# Sender_Power.net
KiCad netlist of a schematic drawn in Altium Designer
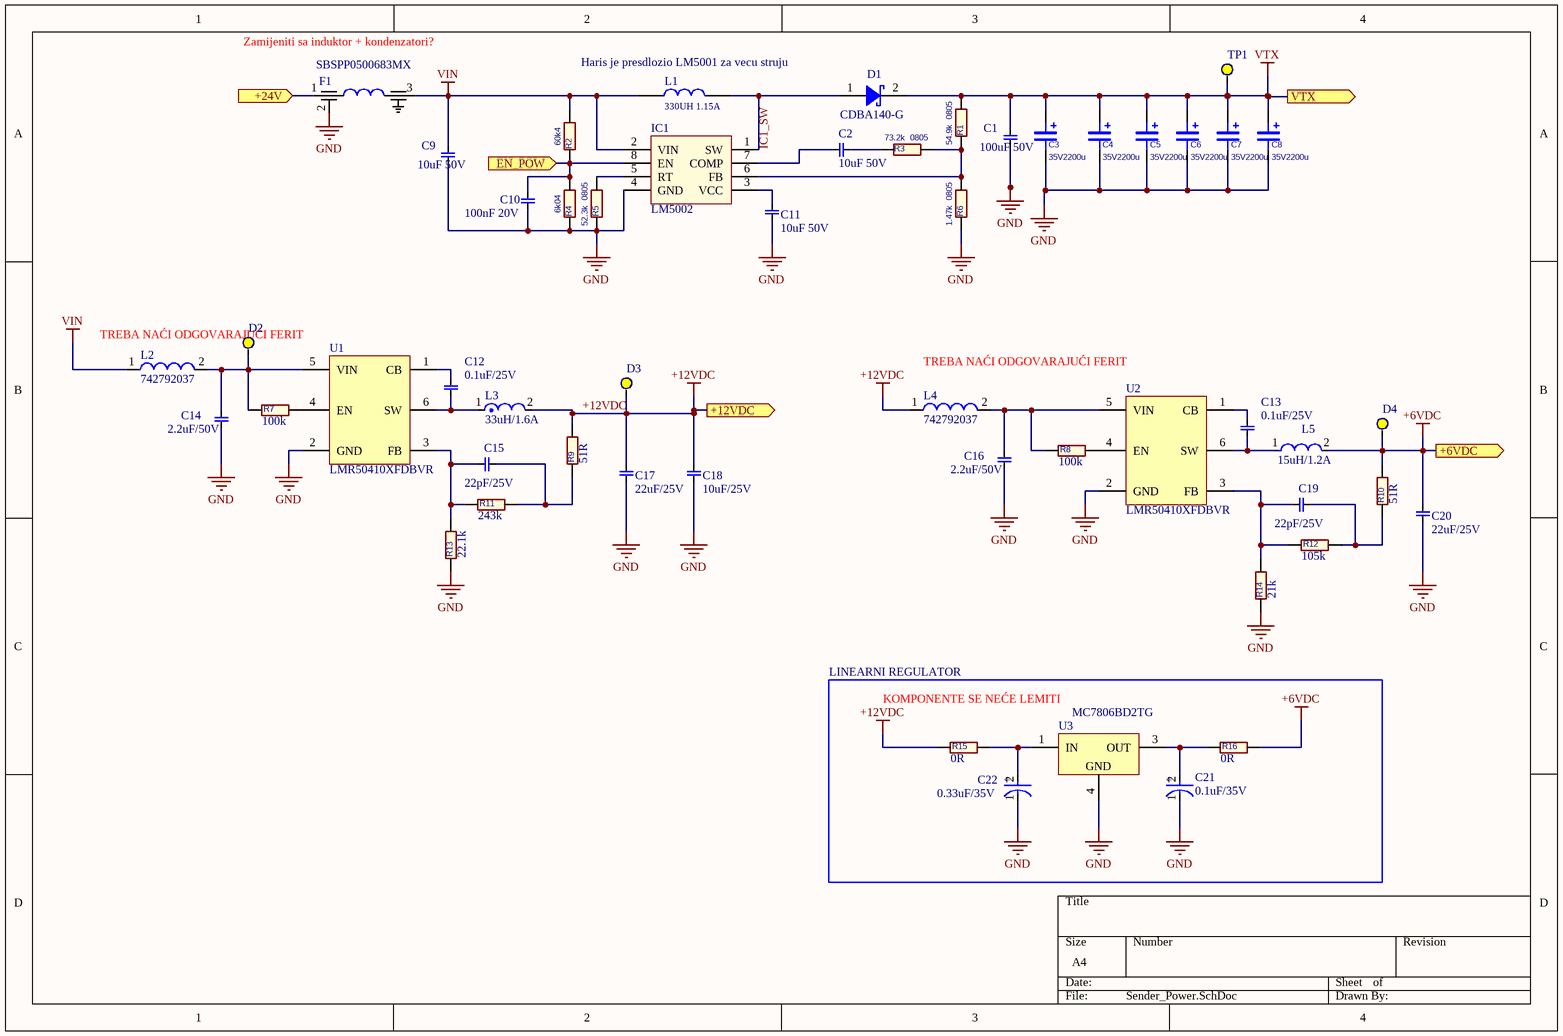
[diagram p0: Sender_Power.SchDoc]

(export (version "E")
  (design (tool "Eeschema 10.0.6"))
  (components
    (comp (ref "C1")
      (value "100uF 50V")
      (footprint "C-0805")
      (fields (field (name "TOLERANCE") "±10%"))
      (libsource (lib "Elreg_Sender") (part "C-0805_10uF"))
    )
    (comp (ref "C2")
      (value "10uF 50V")
      (footprint "C-0603")
      (fields (field (name "TOLERANCE") "±10%"))
      (libsource (lib "Elreg_Sender") (part "C-0805_10uF"))
    )
    (comp (ref "C3")
      (value "35V2200u")
      (footprint "CAP_16X25")
      (description "Capacitor")
      (fields
        (field (name "MANUFACTURER") "Kemet")
        (field (name "MANUFACTURER PART NUMBER") "ESH228M035AM7AA")
      )
      (libsource (lib "Elreg_Sender") (part "CAP_2200uF_35V"))
    )
    (comp (ref "C4")
      (value "35V2200u")
      (footprint "CAP_16X25")
      (description "Capacitor")
      (fields
        (field (name "MANUFACTURER") "Kemet")
        (field (name "MANUFACTURER PART NUMBER") "ESH228M035AM7AA")
      )
      (libsource (lib "Elreg_Sender") (part "CAP_2200uF_35V"))
    )
    (comp (ref "C5")
      (value "35V2200u")
      (footprint "CAP_16X25")
      (description "Capacitor")
      (fields
        (field (name "MANUFACTURER") "Kemet")
        (field (name "MANUFACTURER PART NUMBER") "ESH228M035AM7AA")
      )
      (libsource (lib "Elreg_Sender") (part "CAP_2200uF_35V"))
    )
    (comp (ref "C6")
      (value "35V2200u")
      (footprint "CAP_16X25")
      (description "Capacitor")
      (fields
        (field (name "MANUFACTURER") "Kemet")
        (field (name "MANUFACTURER PART NUMBER") "ESH228M035AM7AA")
      )
      (libsource (lib "Elreg_Sender") (part "CAP_2200uF_35V"))
    )
    (comp (ref "C7")
      (value "35V2200u")
      (footprint "CAP_16X25")
      (description "Capacitor")
      (fields
        (field (name "MANUFACTURER") "Kemet")
        (field (name "MANUFACTURER PART NUMBER") "ESH228M035AM7AA")
      )
      (libsource (lib "Elreg_Sender") (part "CAP_2200uF_35V"))
    )
    (comp (ref "C8")
      (value "35V2200u")
      (footprint "CAP_16X25")
      (description "Capacitor")
      (fields
        (field (name "MANUFACTURER") "Kemet")
        (field (name "MANUFACTURER PART NUMBER") "ESH228M035AM7AA")
      )
      (libsource (lib "Elreg_Sender") (part "CAP_2200uF_35V"))
    )
    (comp (ref "C9")
      (value "10uF 50V")
      (footprint "C-0805")
      (fields (field (name "TOLERANCE") "±10%"))
      (libsource (lib "Elreg_Sender") (part "C-0805_10uF"))
    )
    (comp (ref "C10")
      (value "100nF 20V")
      (footprint "C-0603")
      (fields (field (name "TOLERANCE") "±10%"))
      (libsource (lib "Elreg_Sender") (part "C-0805_100nF"))
    )
    (comp (ref "C11")
      (value "10uF 50V")
      (footprint "C-0603")
      (fields (field (name "TOLERANCE") "±10%"))
      (libsource (lib "Elreg_Sender") (part "C-0805_10uF"))
    )
    (comp (ref "C12")
      (value "0.1uF/25V")
      (footprint "C-0603")
      (description "0.1µF ±5% 25V Ceramic Capacitor X7R 0603 (1608 Metric)")
      (fields
        (field (name "MANUFACTURER") "Kyocera AVX")
        (field (name "MANUFACTURER PART NUMBER") "06033C104JAZ2A")
      )
      (libsource (lib "New_Library") (part "06033C104JAZ2A"))
    )
    (comp (ref "C13")
      (value "0.1uF/25V")
      (footprint "C-0603")
      (description "0.1µF ±5% 25V Ceramic Capacitor X7R 0603 (1608 Metric)")
      (fields
        (field (name "MANUFACTURER") "Kyocera AVX")
        (field (name "MANUFACTURER PART NUMBER") "06033C104JAZ2A")
      )
      (libsource (lib "New_Library") (part "06033C104JAZ2A"))
    )
    (comp (ref "C14")
      (value "2.2uF/50V")
      (footprint "FP-CL31-IPC_B")
      (description "Cap Ceramic 2.2uF 50V X7R ±10% SMD 1206 +125°C Embossed T/R")
      (fields (field (name "TOLERANCE") "10%"))
      (libsource (lib "New_Library") (part "CL31B225KBHVPNE"))
    )
    (comp (ref "C15")
      (value "22pF/25V")
      (footprint "C-0603")
      (description "22pF ±10% 25V Ceramic Capacitor C0G, NP0 0603 (1608 Metric)")
      (fields
        (field (name "MANUFACTURER") "KEMET")
        (field (name "MANUFACTURER PART NUMBER") "C0603C220K3GACTU")
      )
      (libsource (lib "New_Library") (part "C0603C220K3GACTU"))
    )
    (comp (ref "C16")
      (value "2.2uF/50V")
      (footprint "FP-CL31-IPC_B")
      (description "Cap Ceramic 2.2uF 50V X7R ±10% SMD 1206 +125°C Embossed T/R")
      (fields (field (name "TOLERANCE") "10%"))
      (libsource (lib "New_Library") (part "CL31B225KBHVPNE"))
    )
    (comp (ref "C17")
      (value "22uF/25V")
      (footprint "CAP-1210")
      (description "22µF ±10% 25V Ceramic Capacitor X7R 1210 (3225 Metric)")
      (fields
        (field (name "MANUFACTURER") "Samsung")
        (field (name "MANUFACTURER PART NUMBER") "CL32B226KAJNNNE")
      )
      (libsource (lib "New_Library") (part "CL32B226KAJNNNE"))
    )
    (comp (ref "C18")
      (value "10uF/25V")
      (footprint "C-1206 (3216 metric)")
      (description "10µF ±10% 25V Ceramic Capacitor X7R 1206 (3216 Metric)")
      (fields
        (field (name "MANUFACTURER") "Samsung")
        (field (name "MANUFACTURER PART NUMBER") "CL31B106KAHNNNE")
      )
      (libsource (lib "New_Library") (part "CL31B106KAHNNNE"))
    )
    (comp (ref "C19")
      (value "22pF/25V")
      (footprint "C-0603")
      (description "22pF ±10% 25V Ceramic Capacitor C0G, NP0 0603 (1608 Metric)")
      (fields
        (field (name "MANUFACTURER") "KEMET")
        (field (name "MANUFACTURER PART NUMBER") "C0603C220K3GACTU")
      )
      (libsource (lib "New_Library") (part "C0603C220K3GACTU"))
    )
    (comp (ref "C20")
      (value "22uF/25V")
      (footprint "CAP-1210")
      (description "22µF ±10% 25V Ceramic Capacitor X7R 1210 (3225 Metric)")
      (fields
        (field (name "MANUFACTURER") "Samsung")
        (field (name "MANUFACTURER PART NUMBER") "CL32B226KAJNNNE")
      )
      (libsource (lib "New_Library") (part "CL32B226KAJNNNE"))
    )
    (comp (ref "C21")
      (value "0.1uF/35V")
      (footprint "FP-UUP1H0R1MCL1GS-MFG")
      (description "0.1µF 50V Aluminum Electrolytic Capacitors Radial, Can - SMD  1000 Hrs @ 105°C")
      (fields (field (name "TOLERANCE") "20%"))
      (libsource (lib "New_Library") (part "UUP1H0R1MCL1GS"))
    )
    (comp (ref "C22")
      (value "0.33uF/35V")
      (footprint "FP-UUP1H0R1MCL1GS-MFG")
      (description "0.33µF 50V Aluminum Electrolytic Capacitors Radial, Can - SMD  2000 Hrs @ 85°C")
      (fields
        (field (name "MANUFACTURER") "Nichicon")
        (field (name "MANUFACTURER PART NUMBER") "UZS1HR33MCL1GB")
      )
      (libsource (lib "New_Library") (part "UZS1HR33MCL1GB"))
    )
    (comp (ref "D1")
      (value "DIODE SCHOTTKY 40V 1A DO214AC")
      (footprint "DFN380P520X45-2N")
      (fields
        (field (name "MANUFACTURER PART NUMBER 1") "CDBA140-G")
        (field (name "BASE PART NUMBER") "CDBA140")
      )
      (libsource (lib "Elreg_Sender") (part "DIODE SCHOTTKY 40V 1A DO214AC"))
    )
    (comp (ref "D2")
      (value "Test_Point")
      (footprint "Test_Point")
      (libsource (lib "New_Library") (part "Test_Point"))
    )
    (comp (ref "D3")
      (value "Test_Point")
      (footprint "Test_Point")
      (libsource (lib "New_Library") (part "Test_Point"))
    )
    (comp (ref "D4")
      (value "Test_Point")
      (footprint "Test_Point")
      (libsource (lib "New_Library") (part "Test_Point"))
    )
    (comp (ref "F1")
      (value "SBSPP0500683MX")
      (footprint "Filter_SBSPP0500")
      (libsource (lib "Elreg_Sender") (part "Filter_SBSPP0500683MX"))
    )
    (comp (ref "IC1")
      (value "LM5002")
      (footprint "SOIC127P600X205-8N")
      (fields (field (name "BASE PART NUMBER") "LM5002"))
      (libsource (lib "New_Library") (part "LM5002"))
    )
    (comp (ref "L1")
      (value "330UH 1.15A")
      (footprint "IND")
      (libsource (lib "Elreg_Sender") (part "FIXED IND 330UH 1.15A 580 MOHM"))
    )
    (comp (ref "L2")
      (value "742792037")
      (footprint "SMD-0805")
      (description "SMD EMI Suppression Ferrite Bead WE-CBF, Z = 330 Ohm")
      (libsource (lib "New_Library") (part "742792037"))
    )
    (comp (ref "L3")
      (value "33uH/1.6A")
      (footprint "FP-DS104C2-MFG")
      (description "Shielded Wirewound Inductor 33uH 20% 1600mA 0.125Ω SMD")
      (fields (field (name "TOLERANCE") "20%"))
      (libsource (lib "New_Library") (part "#B952AS-H-330M=P3"))
    )
    (comp (ref "L4")
      (value "742792037")
      (footprint "SMD-0805")
      (description "SMD EMI Suppression Ferrite Bead WE-CBF, Z = 330 Ohm")
      (libsource (lib "New_Library") (part "742792037"))
    )
    (comp (ref "L5")
      (value "15uH/1.2A")
      (footprint "FP-LQH5BPB_T0-MFG")
      (description "15µH Shielded Wirewound Inductor 1.2A 187mOhm Max Nonstandard")
      (fields (field (name "TOLERANCE") "20%"))
      (libsource (lib "New_Library") (part "LQH5BPN150MT0L"))
    )
    (comp (ref "R1")
      (value "54.9k  0805")
      (footprint "R-0603")
      (description "RES xx OHM 1/8W 5% 0805 SMD")
      (libsource (lib "Elreg (Skipper)") (part "CRCW0805xxxxJN Default"))
    )
    (comp (ref "R2")
      (value "60k4")
      (footprint "R-0603")
      (description "RES 1 KOHM 1/8W 1% 0805 SMD")
      (fields (field (name "TOLERANCE") "±1%"))
      (libsource (lib "Elreg (Skipper)") (part "CRCW08051K00FKEA"))
    )
    (comp (ref "R3")
      (value "73.2k  0805")
      (footprint "R-0603")
      (description "RES xx OHM 1/8W 5% 0805 SMD")
      (libsource (lib "") (part "CRCW0805xxxxJN Default_1"))
    )
    (comp (ref "R4")
      (value "6k04")
      (footprint "R-0603")
      (description "RES 1 KOHM 1/8W 1% 0805 SMD")
      (fields (field (name "TOLERANCE") "±1%"))
      (libsource (lib "Elreg (Skipper)") (part "CRCW08051K00FKEA"))
    )
    (comp (ref "R5")
      (value "52.3k  0805")
      (footprint "R-0603")
      (description "RES xx OHM 1/8W 5% 0805 SMD")
      (libsource (lib "Elreg (Skipper)") (part "CRCW0805xxxxJN Default"))
    )
    (comp (ref "R6")
      (value "1.47k  0805")
      (footprint "R-0603")
      (description "RES xx OHM 1/8W 5% 0805 SMD")
      (libsource (lib "Elreg (Skipper)") (part "CRCW0805xxxxJN Default"))
    )
    (comp (ref "R7")
      (value "100k")
      (footprint "R-0603")
      (description "100 kOhms ±0.5% 0.063W, 1/16W Chip Resistor 0603 (1608 Metric)  Thin Film")
      (fields
        (field (name "MANUFACTURER") "Susumu")
        (field (name "MANUFACTURER PART NUMBER") "RR0816P-104-D")
      )
      (libsource (lib "New_Library") (part "RR0816P-104-D"))
    )
    (comp (ref "R8")
      (value "100k")
      (footprint "R-0603")
      (description "100 kOhms ±0.5% 0.063W, 1/16W Chip Resistor 0603 (1608 Metric)  Thin Film")
      (fields
        (field (name "MANUFACTURER") "Susumu")
        (field (name "MANUFACTURER PART NUMBER") "RR0816P-104-D")
      )
      (libsource (lib "New_Library") (part "RR0816P-104-D"))
    )
    (comp (ref "R9")
      (value "51R")
      (footprint "R-0603")
      (description "51 Ohms ±0.5% 0.063W, 1/16W Chip Resistor 0603 (1608 Metric)  Thin Film")
      (fields
        (field (name "MANUFACTURER") "Susumu")
        (field (name "MANUFACTURER PART NUMBER") "RR0816Q-510-D")
      )
      (libsource (lib "New_Library") (part "RR0816Q-510-D"))
    )
    (comp (ref "R10")
      (value "51R")
      (footprint "R-0603")
      (description "51 Ohms ±0.5% 0.063W, 1/16W Chip Resistor 0603 (1608 Metric)  Thin Film")
      (fields
        (field (name "MANUFACTURER") "Susumu")
        (field (name "MANUFACTURER PART NUMBER") "RR0816Q-510-D")
      )
      (libsource (lib "New_Library") (part "RR0816Q-510-D"))
    )
    (comp (ref "R11")
      (value "243k")
      (footprint "R-0603")
      (description "243 kOhms ±0.5% 0.063W, 1/16W Chip Resistor 0603 (1608 Metric)  Thin Film")
      (fields
        (field (name "MANUFACTURER") "Susumu")
        (field (name "MANUFACTURER PART NUMBER") "RR0816P-2433-D-38D")
      )
      (libsource (lib "New_Library") (part "RR0816P-2433-D-38D"))
    )
    (comp (ref "R12")
      (value "105k")
      (footprint "R-0603")
      (description "105 kOhms ±0.1% 0.063W, 1/16W Chip Resistor 0603 (1608 Metric)  Thin Film")
      (fields
        (field (name "MANUFACTURER") "TE Connectivity")
        (field (name "MANUFACTURER PART NUMBER") "RN73C1J105KBTDF")
      )
      (libsource (lib "New_Library") (part "RN73C1J105KBTD"))
    )
    (comp (ref "R13")
      (value "22.1k")
      (footprint "R-0603")
      (description "22.1 kOhms ±0.5% 0.063W, 1/16W Chip Resistor 0603 (1608 Metric)  Thin Film")
      (fields
        (field (name "MANUFACTURER") "Susumu")
        (field (name "MANUFACTURER PART NUMBER") "RR0816P-2212-D-34C")
      )
      (libsource (lib "New_Library") (part "RR0816P-2212-D-34C"))
    )
    (comp (ref "R14")
      (value "21k")
      (footprint "R-0603")
      (description "21 kOhms ±0.5% 0.063W, 1/16W Chip Resistor 0603 (1608 Metric)  Thin Film")
      (fields
        (field (name "MANUFACTURER") "Susumu")
        (field (name "MANUFACTURER PART NUMBER") "RR0816P-2102-D-32C")
      )
      (libsource (lib "New_Library") (part "RR0816P-2102-D-32C"))
    )
    (comp (ref "R15")
      (value "0R")
      (footprint "RES-0805")
      (description "0 Ohms Jumper 0.125W, 1/8W Chip Resistor 0805 (2012 Metric) Moisture Resistant Thick Film")
      (libsource (lib "New_Library") (part "RC0805JR-070RL"))
    )
    (comp (ref "R16")
      (value "0R")
      (footprint "RES-0805")
      (description "0 Ohms Jumper 0.125W, 1/8W Chip Resistor 0805 (2012 Metric) Moisture Resistant Thick Film")
      (libsource (lib "New_Library") (part "RC0805JR-070RL"))
    )
    (comp (ref "TP1")
      (value "Test_Point")
      (footprint "Test_Point")
      (libsource (lib "New_Library") (part "Test_Point"))
    )
    (comp (ref "U1")
      (value "LMR50410XFDBVR")
      (footprint "SOT-23")
      (description "Buck Switching Regulator IC Positive Adjustable 1V 1 Output 1A SOT-23-6")
      (fields (field (name "MANUFACTURER") "Texas Instruments"))
      (libsource (lib "New_Library") (part "LMR50410XFDBVR"))
    )
    (comp (ref "U2")
      (value "LMR50410XFDBVR")
      (footprint "SOT-23")
      (description "Buck Switching Regulator IC Positive Adjustable 1V 1 Output 1A SOT-23-6")
      (fields (field (name "MANUFACTURER") "Texas Instruments"))
      (libsource (lib "New_Library") (part "LMR50410XFDBVR"))
    )
    (comp (ref "U3")
      (value "MC7806BD2TG")
      (footprint "D2PAK")
      (description "IC REG LINEAR 6V 1A D2PAK")
      (fields (field (name "MANUFACTURER") "ON Semiconductor"))
      (libsource (lib "New_Library") (part "MC7806BD2TG"))
    )
  )
  (nets
    (net (code "1") (name "+6VDC") (class "Default")
      (node (ref "C20") (pin "2") (pinfunction "G_2") (pintype "passive"))
      (node (ref "D4") (pin "1") (pinfunction "1_1") (pintype "passive"))
      (node (ref "L5") (pin "2") (pinfunction "2_2") (pintype "passive"))
      (node (ref "R10") (pin "2") (pinfunction "2_2") (pintype "passive"))
      (node (ref "R16") (pin "2") (pinfunction "2_2") (pintype "passive"))
    )
    (net (code "2") (name "+12VDC") (class "Default")
      (node (ref "C17") (pin "2") (pinfunction "G_2") (pintype "passive"))
      (node (ref "C18") (pin "1") (pinfunction "G_1") (pintype "passive"))
      (node (ref "D3") (pin "1") (pinfunction "1_1") (pintype "passive"))
      (node (ref "L3") (pin "2") (pinfunction "2_2") (pintype "passive"))
      (node (ref "L4") (pin "1") (pinfunction "1_1") (pintype "passive"))
      (node (ref "R15") (pin "1") (pinfunction "1_1") (pintype "passive"))
      (node (ref "R9") (pin "2") (pinfunction "2_2") (pintype "passive"))
    )
    (net (code "3") (name "/+24V") (class "Default")
      (node (ref "F1") (pin "1") (pinfunction "1_1") (pintype "passive"))
    )
    (net (code "4") (name "/EN_POW") (class "Default")
      (node (ref "C10") (pin "2") (pinfunction "G_2") (pintype "passive"))
      (node (ref "IC1") (pin "8") (pinfunction "EN_8") (pintype "passive"))
      (node (ref "R2") (pin "1") (pinfunction "1_1") (pintype "passive"))
      (node (ref "R4") (pin "2") (pinfunction "2_2") (pintype "passive"))
    )
    (net (code "6") (name "GND") (class "Default")
      (node (ref "C1") (pin "2") (pinfunction "G_2") (pintype "passive"))
      (node (ref "C10") (pin "1") (pinfunction "G_1") (pintype "passive"))
      (node (ref "C11") (pin "2") (pinfunction "G_2") (pintype "passive"))
      (node (ref "C14") (pin "1") (pinfunction "G_1") (pintype "passive"))
      (node (ref "C16") (pin "1") (pinfunction "G_1") (pintype "passive"))
      (node (ref "C17") (pin "1") (pinfunction "G_1") (pintype "passive"))
      (node (ref "C18") (pin "2") (pinfunction "G_2") (pintype "passive"))
      (node (ref "C20") (pin "1") (pinfunction "G_1") (pintype "passive"))
      (node (ref "C21") (pin "1") (pinfunction "C_1") (pintype "passive"))
      (node (ref "C22") (pin "1") (pinfunction "C_1") (pintype "passive"))
      (node (ref "C3") (pin "2") (pinfunction "2_2") (pintype "passive"))
      (node (ref "C4") (pin "2") (pinfunction "2_2") (pintype "passive"))
      (node (ref "C5") (pin "2") (pinfunction "2_2") (pintype "passive"))
      (node (ref "C6") (pin "2") (pinfunction "2_2") (pintype "passive"))
      (node (ref "C7") (pin "2") (pinfunction "2_2") (pintype "passive"))
      (node (ref "C8") (pin "2") (pinfunction "2_2") (pintype "passive"))
      (node (ref "C9") (pin "2") (pinfunction "G_2") (pintype "passive"))
      (node (ref "F1") (pin "2") (pinfunction "2_2") (pintype "passive"))
      (node (ref "IC1") (pin "4") (pinfunction "GND_4") (pintype "passive"))
      (node (ref "R13") (pin "1") (pinfunction "1_1") (pintype "passive"))
      (node (ref "R14") (pin "1") (pinfunction "1_1") (pintype "passive"))
      (node (ref "R4") (pin "1") (pinfunction "1_1") (pintype "passive"))
      (node (ref "R5") (pin "1") (pinfunction "1_1") (pintype "passive"))
      (node (ref "R6") (pin "1") (pinfunction "1_1") (pintype "passive"))
      (node (ref "U1") (pin "2") (pinfunction "GND_2") (pintype "passive"))
      (node (ref "U2") (pin "2") (pinfunction "GND_2") (pintype "passive"))
      (node (ref "U3") (pin "4") (pinfunction "GND_4") (pintype "power_in"))
    )
    (net (code "7") (name "Net-(C2-G-Pad2)") (class "Default")
      (node (ref "C2") (pin "2") (pinfunction "G_2") (pintype "passive"))
      (node (ref "R3") (pin "1") (pinfunction "1_1") (pintype "passive"))
    )
    (net (code "8") (name "Net-(C15-G-Pad2)") (class "Default")
      (node (ref "C15") (pin "2") (pinfunction "G_2") (pintype "passive"))
      (node (ref "R11") (pin "2") (pinfunction "2_2") (pintype "passive"))
      (node (ref "R9") (pin "1") (pinfunction "1_1") (pintype "passive"))
    )
    (net (code "9") (name "Net-(C19-G-Pad2)") (class "Default")
      (node (ref "C19") (pin "2") (pinfunction "G_2") (pintype "passive"))
      (node (ref "R10") (pin "1") (pinfunction "1_1") (pintype "passive"))
      (node (ref "R12") (pin "2") (pinfunction "2_2") (pintype "passive"))
    )
    (net (code "10") (name "Net-(C21-A)") (class "Default")
      (node (ref "C21") (pin "2") (pinfunction "A_2") (pintype "passive"))
      (node (ref "R16") (pin "1") (pinfunction "1_1") (pintype "passive"))
      (node (ref "U3") (pin "3") (pinfunction "OUT_3") (pintype "power_in"))
    )
    (net (code "11") (name "Net-(C22-A)") (class "Default")
      (node (ref "C22") (pin "2") (pinfunction "A_2") (pintype "passive"))
      (node (ref "R15") (pin "2") (pinfunction "2_2") (pintype "passive"))
      (node (ref "U3") (pin "1") (pinfunction "IN_1") (pintype "power_in"))
    )
    (net (code "12") (name "Net-(IC1-COMP)") (class "Default")
      (node (ref "C2") (pin "1") (pinfunction "G_1") (pintype "passive"))
      (node (ref "IC1") (pin "7") (pinfunction "COMP_7") (pintype "passive"))
    )
    (net (code "13") (name "Net-(IC1-FB)") (class "Default")
      (node (ref "IC1") (pin "6") (pinfunction "FB_6") (pintype "passive"))
      (node (ref "R1") (pin "1") (pinfunction "1_1") (pintype "passive"))
      (node (ref "R3") (pin "2") (pinfunction "2_2") (pintype "passive"))
      (node (ref "R6") (pin "2") (pinfunction "2_2") (pintype "passive"))
    )
    (net (code "14") (name "Net-(IC1-RT)") (class "Default")
      (node (ref "IC1") (pin "5") (pinfunction "RT_5") (pintype "passive"))
      (node (ref "R5") (pin "2") (pinfunction "2_2") (pintype "passive"))
    )
    (net (code "15") (name "Net-(IC1-SW)") (class "Default")
      (node (ref "D1") (pin "1") (pinfunction "A_1") (pintype "passive"))
      (node (ref "IC1") (pin "1") (pinfunction "SW_1") (pintype "passive"))
      (node (ref "L1") (pin "2") (pinfunction "A_2") (pintype "passive"))
    )
    (net (code "16") (name "Net-(IC1-VCC)") (class "Default")
      (node (ref "C11") (pin "1") (pinfunction "G_1") (pintype "passive"))
      (node (ref "IC1") (pin "3") (pinfunction "VCC_3") (pintype "passive"))
    )
    (net (code "17") (name "Net-(U1-CB)") (class "Default")
      (node (ref "C12") (pin "2") (pinfunction "G_2") (pintype "passive"))
      (node (ref "U1") (pin "1") (pinfunction "CB_1") (pintype "passive"))
    )
    (net (code "18") (name "Net-(U1-EN)") (class "Default")
      (node (ref "R7") (pin "2") (pinfunction "2_2") (pintype "passive"))
      (node (ref "U1") (pin "4") (pinfunction "EN_4") (pintype "passive"))
    )
    (net (code "19") (name "Net-(U1-FB)") (class "Default")
      (node (ref "C15") (pin "1") (pinfunction "G_1") (pintype "passive"))
      (node (ref "R11") (pin "1") (pinfunction "1_1") (pintype "passive"))
      (node (ref "R13") (pin "2") (pinfunction "2_2") (pintype "passive"))
      (node (ref "U1") (pin "3") (pinfunction "FB_3") (pintype "passive"))
    )
    (net (code "20") (name "Net-(U1-SW)") (class "Default")
      (node (ref "C12") (pin "1") (pinfunction "G_1") (pintype "passive"))
      (node (ref "L3") (pin "1") (pinfunction "1_1") (pintype "passive"))
      (node (ref "U1") (pin "6") (pinfunction "SW_6") (pintype "passive"))
    )
    (net (code "21") (name "Net-(U1-VIN)") (class "Default")
      (node (ref "C14") (pin "2") (pinfunction "G_2") (pintype "passive"))
      (node (ref "D2") (pin "1") (pinfunction "1_1") (pintype "passive"))
      (node (ref "L2") (pin "2") (pinfunction "2_2") (pintype "passive"))
      (node (ref "R7") (pin "1") (pinfunction "1_1") (pintype "passive"))
      (node (ref "U1") (pin "5") (pinfunction "VIN_5") (pintype "passive"))
    )
    (net (code "22") (name "Net-(U2-CB)") (class "Default")
      (node (ref "C13") (pin "2") (pinfunction "G_2") (pintype "passive"))
      (node (ref "U2") (pin "1") (pinfunction "CB_1") (pintype "passive"))
    )
    (net (code "23") (name "Net-(U2-EN)") (class "Default")
      (node (ref "R8") (pin "2") (pinfunction "2_2") (pintype "passive"))
      (node (ref "U2") (pin "4") (pinfunction "EN_4") (pintype "passive"))
    )
    (net (code "24") (name "Net-(U2-FB)") (class "Default")
      (node (ref "C19") (pin "1") (pinfunction "G_1") (pintype "passive"))
      (node (ref "R12") (pin "1") (pinfunction "1_1") (pintype "passive"))
      (node (ref "R14") (pin "2") (pinfunction "2_2") (pintype "passive"))
      (node (ref "U2") (pin "3") (pinfunction "FB_3") (pintype "passive"))
    )
    (net (code "25") (name "Net-(U2-SW)") (class "Default")
      (node (ref "C13") (pin "1") (pinfunction "G_1") (pintype "passive"))
      (node (ref "L5") (pin "1") (pinfunction "1_1") (pintype "passive"))
      (node (ref "U2") (pin "6") (pinfunction "SW_6") (pintype "passive"))
    )
    (net (code "26") (name "Net-(U2-VIN)") (class "Default")
      (node (ref "C16") (pin "2") (pinfunction "G_2") (pintype "passive"))
      (node (ref "L4") (pin "2") (pinfunction "2_2") (pintype "passive"))
      (node (ref "R8") (pin "1") (pinfunction "1_1") (pintype "passive"))
      (node (ref "U2") (pin "5") (pinfunction "VIN_5") (pintype "passive"))
    )
    (net (code "27") (name "VIN") (class "Default")
      (node (ref "C9") (pin "1") (pinfunction "G_1") (pintype "passive"))
      (node (ref "F1") (pin "3") (pinfunction "3_3") (pintype "passive"))
      (node (ref "IC1") (pin "2") (pinfunction "VIN_2") (pintype "passive"))
      (node (ref "L1") (pin "1") (pinfunction "A_1") (pintype "passive"))
      (node (ref "L2") (pin "1") (pinfunction "1_1") (pintype "passive"))
      (node (ref "R2") (pin "2") (pinfunction "2_2") (pintype "passive"))
    )
    (net (code "28") (name "VTX") (class "Default")
      (node (ref "C1") (pin "1") (pinfunction "G_1") (pintype "passive"))
      (node (ref "C3") (pin "1") (pinfunction "1_1") (pintype "passive"))
      (node (ref "C4") (pin "1") (pinfunction "1_1") (pintype "passive"))
      (node (ref "C5") (pin "1") (pinfunction "1_1") (pintype "passive"))
      (node (ref "C6") (pin "1") (pinfunction "1_1") (pintype "passive"))
      (node (ref "C7") (pin "1") (pinfunction "1_1") (pintype "passive"))
      (node (ref "C8") (pin "1") (pinfunction "1_1") (pintype "passive"))
      (node (ref "D1") (pin "2") (pinfunction "A_2") (pintype "passive"))
      (node (ref "R1") (pin "2") (pinfunction "2_2") (pintype "passive"))
      (node (ref "TP1") (pin "1") (pinfunction "1_1") (pintype "passive"))
    )
  )
)
